# CANbus.net
KiCad netlist of a schematic drawn in Altium Designer
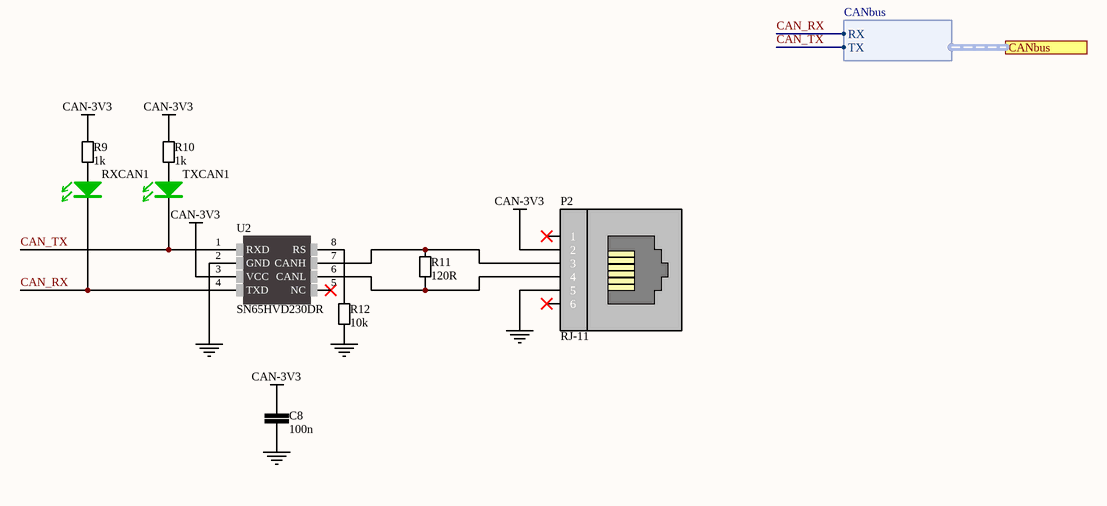
[diagram p0: CANbus.SchDoc]

(export (version "E")
  (design (tool "Eeschema 10.0.6"))
  (components
    (comp (ref "C8")
      (value "100n")
      (footprint "CER_0603")
      (description "CAP CER 100n 10V X5R 10% 0603")
      (libsource (lib "Capacitors") (part "06032105"))
    )
    (comp (ref "P2")
      (value "RJ-11")
      (footprint "RJ11-6N-B")
      (libsource (lib "Electro_Mechanical") (part "00000001"))
    )
    (comp (ref "R9")
      (value "1k")
      (footprint "RESC2013X38N-0805-NOOVERLAY")
      (description "RES SMD 1 kOhm 1/8W 0805")
      (fields (field (name "POWER") "0.125W, 1/8W"))
      (libsource (lib "Resistors") (part "00001001"))
    )
    (comp (ref "R10")
      (value "1k")
      (footprint "RESC2013X38N-0805-NOOVERLAY")
      (description "RES SMD 1 kOhm 1/8W 0805")
      (fields (field (name "POWER") "0.125W, 1/8W"))
      (libsource (lib "Resistors") (part "00001001"))
    )
    (comp (ref "R11")
      (value "120R")
      (footprint "RESC2013X38N-0805-NOOVERLAY")
      (description "RES SMD 120 Ohm 1/8W 0805")
      (libsource (lib "Resistors") (part "000001200"))
    )
    (comp (ref "R12")
      (value "10k")
      (footprint "RESC2013X38N-0805-NOOVERLAY")
      (description "RES SMD 10 kOhm 1/8W 0805")
      (libsource (lib "Resistors") (part "000001002"))
    )
    (comp (ref "RXCAN1")
      (value "LED GREEN")
      (footprint "LED_GREEN_0805")
      (description "LED GREEN CLEAR 0805 SMD")
      (fields
        (field (name "MANUFACTURER") "Kingbright")
        (field (name "MANUFACTURER PART NUMBER") "APT2012SGC")
      )
      (libsource (lib "Discrete_Semiconductor") (part "LED_GREEN 0805"))
    )
    (comp (ref "TXCAN1")
      (value "LED GREEN")
      (footprint "LED_GREEN_0805")
      (description "LED GREEN CLEAR 0805 SMD")
      (fields
        (field (name "MANUFACTURER") "Kingbright")
        (field (name "MANUFACTURER PART NUMBER") "APT2012SGC")
      )
      (libsource (lib "Discrete_Semiconductor") (part "LED_GREEN 0805"))
    )
    (comp (ref "U2")
      (value "SN65HVD230DR")
      (footprint "SOIC-8")
      (description "IC EMC CAN TRANSCEIVER 8-SOIC")
      (libsource (lib "Integrated_circuits") (part "SN65HVD230"))
    )
  )
  (nets
    (net (code "2") (name "/CAN_RX") (class "Default")
      (node (ref "RXCAN1") (pin "1") (pinfunction "C_1") (pintype "passive"))
      (node (ref "U2") (pin "4") (pinfunction "TXD_4") (pintype "passive"))
    )
    (net (code "3") (name "/CAN_TX") (class "Default")
      (node (ref "TXCAN1") (pin "1") (pinfunction "C_1") (pintype "passive"))
      (node (ref "U2") (pin "1") (pinfunction "RXD_1") (pintype "passive"))
    )
    (net (code "5") (name "CAN-3V3") (class "Default")
      (node (ref "C8") (pin "2") (pinfunction "2_2") (pintype "passive"))
      (node (ref "P2") (pin "2") (pinfunction "2_2") (pintype "passive"))
      (node (ref "R10") (pin "2") (pinfunction "2_2") (pintype "passive"))
      (node (ref "R9") (pin "2") (pinfunction "2_2") (pintype "passive"))
      (node (ref "U2") (pin "3") (pinfunction "VCC_3") (pintype "passive"))
    )
    (net (code "6") (name "GND") (class "Default")
      (node (ref "C8") (pin "1") (pinfunction "1_1") (pintype "passive"))
      (node (ref "P2") (pin "5") (pinfunction "5_5") (pintype "passive"))
      (node (ref "R12") (pin "1") (pinfunction "1_1") (pintype "passive"))
      (node (ref "U2") (pin "2") (pinfunction "GND_2") (pintype "passive"))
    )
    (net (code "7") (name "Net-(RXCAN1-A)") (class "Default")
      (node (ref "R9") (pin "1") (pinfunction "1_1") (pintype "passive"))
      (node (ref "RXCAN1") (pin "2") (pinfunction "A_2") (pintype "passive"))
    )
    (net (code "8") (name "Net-(TXCAN1-A)") (class "Default")
      (node (ref "R10") (pin "1") (pinfunction "1_1") (pintype "passive"))
      (node (ref "TXCAN1") (pin "2") (pinfunction "A_2") (pintype "passive"))
    )
    (net (code "9") (name "Net-(U2-CANH)") (class "Default")
      (node (ref "P2") (pin "3") (pinfunction "3_3") (pintype "passive"))
      (node (ref "R11") (pin "1") (pinfunction "1_1") (pintype "passive"))
      (node (ref "U2") (pin "7") (pinfunction "CANH_7") (pintype "passive"))
    )
    (net (code "10") (name "Net-(U2-CANL)") (class "Default")
      (node (ref "P2") (pin "4") (pinfunction "4_4") (pintype "passive"))
      (node (ref "R11") (pin "2") (pinfunction "2_2") (pintype "passive"))
      (node (ref "U2") (pin "6") (pinfunction "CANL_6") (pintype "passive"))
    )
    (net (code "11") (name "Net-(U2-RS)") (class "Default")
      (node (ref "R12") (pin "2") (pinfunction "2_2") (pintype "passive"))
      (node (ref "U2") (pin "8") (pinfunction "RS_8") (pintype "passive"))
    )
    (net (code "12") (name "unconnected-(P2-Pad1)") (class "Default")
      (node (ref "P2") (pin "1") (pinfunction "1_1") (pintype "passive+no_connect"))
    )
    (net (code "13") (name "unconnected-(P2-Pad6)") (class "Default")
      (node (ref "P2") (pin "6") (pinfunction "6_6") (pintype "passive+no_connect"))
    )
    (net (code "14") (name "unconnected-(U2-NC-Pad5)") (class "Default")
      (node (ref "U2") (pin "5") (pinfunction "NC_5") (pintype "passive+no_connect"))
    )
  )
)
